# amplifier.net
KiCad netlist of a schematic drawn in EAGLE
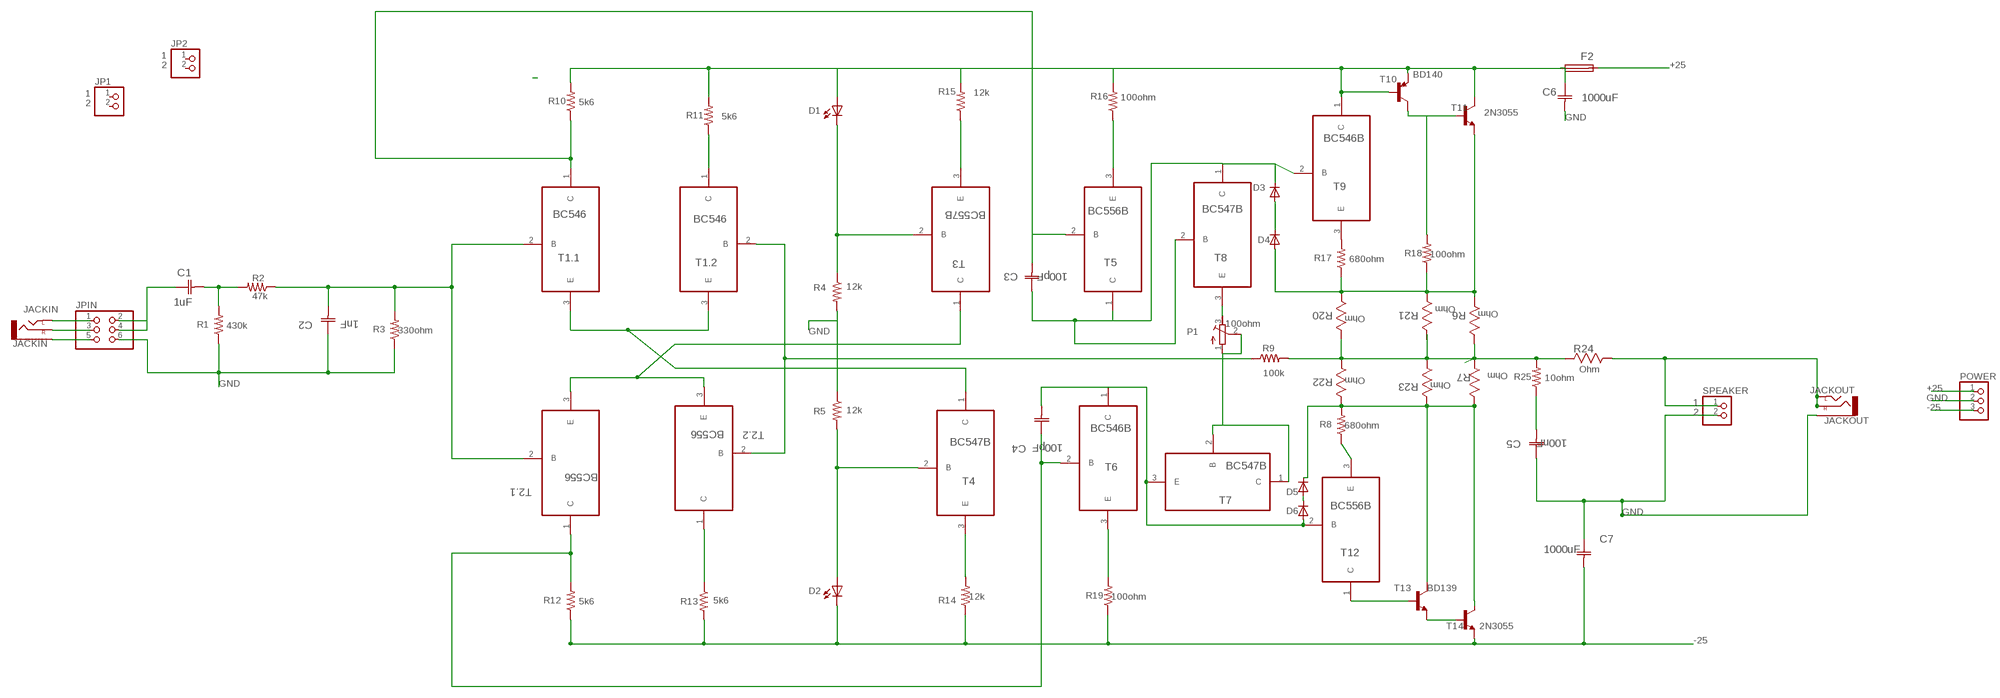
[diagram p0: schematic, sheet 1]

(export (version "E")
  (design (tool "Eeschema 10.0.6"))
  (components
    (comp (ref "C1")
      (value "1uF")
      (footprint "eagle-import:CAPCP3216X180N")
      (fields
        (field (name "MPN") "TPSA226K006R0500")
        (field (name "MPN_1") "TPSA226K006R0500")
        (field (name "OC_FARNELL") "-")
        (field (name "OC_NEWARK") "75M9217")
        (field (name "VOLTAGERATING") "6.3V")
      )
      (libsource (lib "eagle-import") (part "TPSA226K006R0500"))
    )
    (comp (ref "C2")
      (value "1nF")
      (footprint "eagle-import:CAPC2012X130N")
      (fields (field (name "MPN") "0805AC102KAT1A") (field (name "TOLERANCE") "±10%"))
      (libsource (lib "eagle-import") (part "0805AC102KAT1A"))
    )
    (comp (ref "C3")
      (value "100pF")
      (footprint "eagle-import:CAPC2012X130N")
      (fields (field (name "MPN") "0805AC102KAT1A") (field (name "TOLERANCE") "±10%"))
      (libsource (lib "eagle-import") (part "0805AC102KAT1A"))
    )
    (comp (ref "C4")
      (value "100pF")
      (footprint "eagle-import:CAPC2012X130N")
      (fields (field (name "MPN") "0805AC102KAT1A") (field (name "TOLERANCE") "±10%"))
      (libsource (lib "eagle-import") (part "0805AC102KAT1A"))
    )
    (comp (ref "C5")
      (value "100nF")
      (footprint "eagle-import:CAPC2012X130N")
      (fields (field (name "MPN") "0805AC102KAT1A") (field (name "TOLERANCE") "±10%"))
      (libsource (lib "eagle-import") (part "0805AC102KAT1A"))
    )
    (comp (ref "C6")
      (value "1000uF")
      (footprint "eagle-import:CAPC2012X130N")
      (fields (field (name "MPN") "0805AC102KAT1A") (field (name "TOLERANCE") "±10%"))
      (libsource (lib "eagle-import") (part "0805AC102KAT1A"))
    )
    (comp (ref "C7")
      (value "1000uF")
      (footprint "eagle-import:CAPC2012X130N")
      (fields (field (name "MPN") "0805AC102KAT1A") (field (name "TOLERANCE") "±10%"))
      (libsource (lib "eagle-import") (part "0805AC102KAT1A"))
    )
    (comp (ref "D1")
      (value "LED5MM")
      (footprint "eagle-import:LED5MM")
      (libsource (lib "eagle-import") (part "LED5MM"))
    )
    (comp (ref "D2")
      (value "LED5MM")
      (footprint "eagle-import:LED5MM")
      (libsource (lib "eagle-import") (part "LED5MM"))
    )
    (comp (ref "D3")
      (value "1N4148DO35-10")
      (footprint "eagle-import:DO35-10")
      (libsource (lib "eagle-import") (part "1N4148DO35-10"))
    )
    (comp (ref "D4")
      (value "1N4148DO35-10")
      (footprint "eagle-import:DO35-10")
      (libsource (lib "eagle-import") (part "1N4148DO35-10"))
    )
    (comp (ref "D5")
      (value "1N4148DO35-10")
      (footprint "eagle-import:DO35-10")
      (libsource (lib "eagle-import") (part "1N4148DO35-10"))
    )
    (comp (ref "D6")
      (value "1N4148DO35-10")
      (footprint "eagle-import:DO35-10")
      (libsource (lib "eagle-import") (part "1N4148DO35-10"))
    )
    (comp (ref "F2")
      (value "FUSEBLANK_5X20MM")
      (footprint "eagle-import:FUSE_HOLDER_5X20MM")
      (fields (field (name "OC_FARNELL") "unknown") (field (name "OC_NEWARK") "unknown"))
      (libsource (lib "eagle-import") (part "FUSEBLANK_5X20MM"))
    )
    (comp (ref "JACKIN")
      (value "JACKIN")
      (footprint "eagle-import:STEREOJACK2.5MM_STEREOJACK2.5MM")
      (libsource (lib "eagle-import") (part "AUDIO-JACK2.5MM"))
    )
    (comp (ref "JACKOUT")
      (value "JACKOUT")
      (footprint "eagle-import:STEREOJACK2.5MM_STEREOJACK2.5MM")
      (libsource (lib "eagle-import") (part "AUDIO-JACK2.5MM"))
    )
    (comp (ref "JP1")
      (value "PINHD-1X2")
      (footprint "eagle-import:1X02")
      (libsource (lib "eagle-import") (part "PINHD-1X2"))
    )
    (comp (ref "JP2")
      (value "PINHD-1X2")
      (footprint "eagle-import:1X02")
      (libsource (lib "eagle-import") (part "PINHD-1X2"))
    )
    (comp (ref "JPIN")
      (value "PINHD-2X3/90")
      (footprint "eagle-import:2X03_90")
      (libsource (lib "eagle-import") (part "PINHD-2X3/90"))
    )
    (comp (ref "P1")
      (value "100ohm")
      (footprint "eagle-import:RTRIM74X")
      (libsource (lib "eagle-import") (part "R-TRIMM74X"))
    )
    (comp (ref "POWER")
      (value "PINHD-1X3/90")
      (footprint "eagle-import:1X03_90")
      (libsource (lib "eagle-import") (part "PINHD-1X3/90"))
    )
    (comp (ref "R1")
      (value "430k")
      (footprint "eagle-import:AXIAL-0.8")
      (libsource (lib "eagle-import") (part "RESISTORPTH-2W"))
    )
    (comp (ref "R2")
      (value "47k")
      (footprint "eagle-import:AXIAL-0.8")
      (libsource (lib "eagle-import") (part "RESISTORPTH-2W"))
    )
    (comp (ref "R3")
      (value "330ohm")
      (footprint "eagle-import:AXIAL-0.8")
      (libsource (lib "eagle-import") (part "RESISTORPTH-2W"))
    )
    (comp (ref "R4")
      (value "12k")
      (footprint "eagle-import:AXIAL-0.8")
      (libsource (lib "eagle-import") (part "RESISTORPTH-2W"))
    )
    (comp (ref "R5")
      (value "12k")
      (footprint "eagle-import:AXIAL-0.8")
      (libsource (lib "eagle-import") (part "RESISTORPTH-2W"))
    )
    (comp (ref "R6")
      (value "Ohm")
      (footprint "eagle-import:RESC2013X65N")
      (fields (field (name "MPN") "CRM0805-FW-R050ELF") (field (name "TOLERANCE") "±1 %"))
      (libsource (lib "eagle-import") (part "CRM0805-FW-R050ELF"))
    )
    (comp (ref "R7")
      (value "Ohm")
      (footprint "eagle-import:RESC2013X65N")
      (fields (field (name "MPN") "CRM0805-FW-R050ELF") (field (name "TOLERANCE") "±1 %"))
      (libsource (lib "eagle-import") (part "CRM0805-FW-R050ELF"))
    )
    (comp (ref "R8")
      (value "680ohm")
      (footprint "eagle-import:AXIAL-0.8")
      (libsource (lib "eagle-import") (part "RESISTORPTH-2W"))
    )
    (comp (ref "R9")
      (value "100k")
      (footprint "eagle-import:AXIAL-0.8")
      (libsource (lib "eagle-import") (part "RESISTORPTH-2W"))
    )
    (comp (ref "R10")
      (value "5k6")
      (footprint "eagle-import:AXIAL-0.8")
      (libsource (lib "eagle-import") (part "RESISTORPTH-2W"))
    )
    (comp (ref "R11")
      (value "5k6")
      (footprint "eagle-import:AXIAL-0.8")
      (libsource (lib "eagle-import") (part "RESISTORPTH-2W"))
    )
    (comp (ref "R12")
      (value "5k6")
      (footprint "eagle-import:AXIAL-0.8")
      (libsource (lib "eagle-import") (part "RESISTORPTH-2W"))
    )
    (comp (ref "R13")
      (value "5k6")
      (footprint "eagle-import:AXIAL-0.8")
      (libsource (lib "eagle-import") (part "RESISTORPTH-2W"))
    )
    (comp (ref "R14")
      (value "12k")
      (footprint "eagle-import:AXIAL-0.8")
      (libsource (lib "eagle-import") (part "RESISTORPTH-2W"))
    )
    (comp (ref "R15")
      (value "12k")
      (footprint "eagle-import:AXIAL-0.8")
      (libsource (lib "eagle-import") (part "RESISTORPTH-2W"))
    )
    (comp (ref "R16")
      (value "100ohm")
      (footprint "eagle-import:AXIAL-0.8")
      (libsource (lib "eagle-import") (part "RESISTORPTH-2W"))
    )
    (comp (ref "R17")
      (value "680ohm")
      (footprint "eagle-import:AXIAL-0.8")
      (libsource (lib "eagle-import") (part "RESISTORPTH-2W"))
    )
    (comp (ref "R18")
      (value "100ohm")
      (footprint "eagle-import:AXIAL-0.8")
      (libsource (lib "eagle-import") (part "RESISTORPTH-2W"))
    )
    (comp (ref "R19")
      (value "100ohm")
      (footprint "eagle-import:AXIAL-0.8")
      (libsource (lib "eagle-import") (part "RESISTORPTH-2W"))
    )
    (comp (ref "R20")
      (value "Ohm")
      (footprint "eagle-import:RESC2013X65N")
      (fields (field (name "MPN") "CRM0805-FW-R050ELF") (field (name "TOLERANCE") "±1 %"))
      (libsource (lib "eagle-import") (part "CRM0805-FW-R050ELF"))
    )
    (comp (ref "R21")
      (value "Ohm")
      (footprint "eagle-import:RESC2013X65N")
      (fields (field (name "MPN") "CRM0805-FW-R050ELF") (field (name "TOLERANCE") "±1 %"))
      (libsource (lib "eagle-import") (part "CRM0805-FW-R050ELF"))
    )
    (comp (ref "R22")
      (value "Ohm")
      (footprint "eagle-import:RESC2013X65N")
      (fields (field (name "MPN") "CRM0805-FW-R050ELF") (field (name "TOLERANCE") "±1 %"))
      (libsource (lib "eagle-import") (part "CRM0805-FW-R050ELF"))
    )
    (comp (ref "R23")
      (value "Ohm")
      (footprint "eagle-import:RESC2013X65N")
      (fields (field (name "MPN") "CRM0805-FW-R050ELF") (field (name "TOLERANCE") "±1 %"))
      (libsource (lib "eagle-import") (part "CRM0805-FW-R050ELF"))
    )
    (comp (ref "R24")
      (value "Ohm")
      (footprint "eagle-import:RESC2013X65N")
      (fields (field (name "MPN") "CRM0805-FW-R050ELF") (field (name "TOLERANCE") "±1 %"))
      (libsource (lib "eagle-import") (part "CRM0805-FW-R050ELF"))
    )
    (comp (ref "R25")
      (value "10ohm")
      (footprint "eagle-import:AXIAL-0.8")
      (libsource (lib "eagle-import") (part "RESISTORPTH-2W"))
    )
    (comp (ref "SPEAKER")
      (value "PINHD-1X2/90")
      (footprint "eagle-import:1X02_90")
      (libsource (lib "eagle-import") (part "PINHD-1X2/90"))
    )
    (comp (ref "T1.1")
      (value "BC546")
      (footprint "eagle-import:TO127P254X732-3")
      (fields (field (name "MPN") "BC546B"))
      (libsource (lib "eagle-import") (part "BC546B"))
    )
    (comp (ref "T1.2")
      (value "BC546")
      (footprint "eagle-import:TO127P254X732-3")
      (fields (field (name "MPN") "BC546B"))
      (libsource (lib "eagle-import") (part "BC546B"))
    )
    (comp (ref "T2.1")
      (value "BC556")
      (footprint "eagle-import:TO127P254X732-3")
      (fields (field (name "MPN") "BC556B"))
      (libsource (lib "eagle-import") (part "BC556B"))
    )
    (comp (ref "T2.2")
      (value "BC556")
      (footprint "eagle-import:TO127P254X732-3")
      (fields (field (name "MPN") "BC556B"))
      (libsource (lib "eagle-import") (part "BC556B"))
    )
    (comp (ref "T3")
      (value "BC557B")
      (footprint "eagle-import:TO127P254X732-3")
      (libsource (lib "eagle-import") (part "BC557B"))
    )
    (comp (ref "T4")
      (value "BC547B")
      (footprint "eagle-import:TO127P254X732-3")
      (libsource (lib "eagle-import") (part "BC547B"))
    )
    (comp (ref "T5")
      (value "BC556B")
      (footprint "eagle-import:TO127P254X732-3")
      (libsource (lib "eagle-import") (part "BC556B"))
    )
    (comp (ref "T6")
      (value "BC546B")
      (footprint "eagle-import:TO127P254X732-3")
      (libsource (lib "eagle-import") (part "BC546B"))
    )
    (comp (ref "T7")
      (value "BC547B")
      (footprint "eagle-import:TO127P254X732-3")
      (libsource (lib "eagle-import") (part "BC547B"))
    )
    (comp (ref "T8")
      (value "BC547B")
      (footprint "eagle-import:TO127P254X732-3")
      (libsource (lib "eagle-import") (part "BC547B"))
    )
    (comp (ref "T9")
      (value "BC546B")
      (footprint "eagle-import:TO127P254X732-3")
      (libsource (lib "eagle-import") (part "BC546B"))
    )
    (comp (ref "T10")
      (value "BD140")
      (footprint "eagle-import:TO126")
      (libsource (lib "eagle-import") (part "BD140"))
    )
    (comp (ref "T11")
      (value "2N3055")
      (footprint "eagle-import:TO3")
      (libsource (lib "eagle-import") (part "2N3055"))
    )
    (comp (ref "T12")
      (value "BC556B")
      (footprint "eagle-import:TO127P254X732-3")
      (libsource (lib "eagle-import") (part "BC556B"))
    )
    (comp (ref "T13")
      (value "BD139")
      (footprint "eagle-import:TO126")
      (libsource (lib "eagle-import") (part "BD139"))
    )
    (comp (ref "T14")
      (value "2N3055")
      (footprint "eagle-import:TO3")
      (libsource (lib "eagle-import") (part "2N3055"))
    )
  )
  (nets
    (net (code "1") (name "/+25") (class "Default")
      (node (ref "F2") (pin "2") (pinfunction "2_2") (pintype "passive"))
      (node (ref "POWER") (pin "1") (pinfunction "1_1") (pintype "passive"))
    )
    (net (code "2") (name "/-25") (class "Default")
      (node (ref "C7") (pin "2") (pinfunction "C2_2") (pintype "passive"))
      (node (ref "D2") (pin "K") (pinfunction "C_K") (pintype "passive"))
      (node (ref "POWER") (pin "3") (pinfunction "3_3") (pintype "passive"))
      (node (ref "R12") (pin "P$1") (pinfunction "1_P$1") (pintype "passive"))
      (node (ref "R13") (pin "P$2") (pinfunction "2_P$2") (pintype "passive"))
      (node (ref "R14") (pin "P$1") (pinfunction "1_P$1") (pintype "passive"))
      (node (ref "R19") (pin "P$1") (pinfunction "1_P$1") (pintype "passive"))
      (node (ref "T14") (pin "E") (pinfunction "E_E") (pintype "passive"))
    )
    (net (code "3") (name "/GND") (class "Default")
      (node (ref "C2") (pin "1") (pinfunction "C1_1") (pintype "passive"))
      (node (ref "C5") (pin "1") (pinfunction "C1_1") (pintype "passive"))
      (node (ref "C6") (pin "2") (pinfunction "C2_2") (pintype "passive"))
      (node (ref "C7") (pin "1") (pinfunction "C1_1") (pintype "passive"))
      (node (ref "JACKOUT") (pin "RING1") (pinfunction "SLEEVE_RING1") (pintype "bidirectional"))
      (node (ref "JPIN") (pin "6") (pinfunction "6_6") (pintype "passive"))
      (node (ref "POWER") (pin "2") (pinfunction "2_2") (pintype "passive"))
      (node (ref "R1") (pin "P$1") (pinfunction "1_P$1") (pintype "passive"))
      (node (ref "R3") (pin "P$1") (pinfunction "1_P$1") (pintype "passive"))
      (node (ref "R4") (pin "P$2") (pinfunction "2_P$2") (pintype "passive"))
      (node (ref "R5") (pin "P$1") (pinfunction "1_P$1") (pintype "passive"))
      (node (ref "SPEAKER") (pin "2") (pinfunction "2_2") (pintype "passive"))
    )
    (net (code "4") (name "Net-(C1-C1)") (class "Default")
      (node (ref "C1") (pin "1") (pinfunction "C1_1") (pintype "passive"))
      (node (ref "JPIN") (pin "2") (pinfunction "2_2") (pintype "passive"))
      (node (ref "JPIN") (pin "4") (pinfunction "4_4") (pintype "passive"))
    )
    (net (code "5") (name "Net-(C1-C2)") (class "Default")
      (node (ref "C1") (pin "2") (pinfunction "C2_2") (pintype "passive"))
      (node (ref "R1") (pin "P$2") (pinfunction "2_P$2") (pintype "passive"))
      (node (ref "R2") (pin "P$2") (pinfunction "2_P$2") (pintype "passive"))
    )
    (net (code "6") (name "Net-(C2-C2)") (class "Default")
      (node (ref "C2") (pin "2") (pinfunction "C2_2") (pintype "passive"))
      (node (ref "R2") (pin "P$1") (pinfunction "1_P$1") (pintype "passive"))
      (node (ref "R3") (pin "P$2") (pinfunction "2_P$2") (pintype "passive"))
      (node (ref "T1.1") (pin "2") (pinfunction "B_2") (pintype "passive"))
      (node (ref "T2.1") (pin "2") (pinfunction "B_2") (pintype "passive"))
    )
    (net (code "7") (name "Net-(C3-C1)") (class "Default")
      (node (ref "C3") (pin "1") (pinfunction "C1_1") (pintype "passive"))
      (node (ref "D3") (pin "C") (pinfunction "C_C") (pintype "passive"))
      (node (ref "T5") (pin "1") (pinfunction "C_1") (pintype "passive"))
      (node (ref "T8") (pin "1") (pinfunction "C_1") (pintype "passive"))
      (node (ref "T8") (pin "2") (pinfunction "B_2") (pintype "passive"))
      (node (ref "T9") (pin "2") (pinfunction "B_2") (pintype "passive"))
    )
    (net (code "8") (name "Net-(C3-C2)") (class "Default")
      (node (ref "C3") (pin "2") (pinfunction "C2_2") (pintype "passive"))
      (node (ref "R10") (pin "P$1") (pinfunction "1_P$1") (pintype "passive"))
      (node (ref "T1.1") (pin "1") (pinfunction "C_1") (pintype "passive"))
      (node (ref "T5") (pin "2") (pinfunction "B_2") (pintype "passive"))
    )
    (net (code "9") (name "Net-(C4-C1)") (class "Default")
      (node (ref "C4") (pin "1") (pinfunction "C1_1") (pintype "passive"))
      (node (ref "R12") (pin "P$2") (pinfunction "2_P$2") (pintype "passive"))
      (node (ref "T2.1") (pin "1") (pinfunction "C_1") (pintype "passive"))
      (node (ref "T6") (pin "2") (pinfunction "B_2") (pintype "passive"))
    )
    (net (code "10") (name "Net-(C4-C2)") (class "Default")
      (node (ref "C4") (pin "2") (pinfunction "C2_2") (pintype "passive"))
      (node (ref "D6") (pin "A") (pinfunction "A_A") (pintype "passive"))
      (node (ref "T12") (pin "2") (pinfunction "B_2") (pintype "passive"))
      (node (ref "T6") (pin "1") (pinfunction "C_1") (pintype "passive"))
      (node (ref "T7") (pin "3") (pinfunction "E_3") (pintype "passive"))
    )
    (net (code "11") (name "Net-(C5-C2)") (class "Default")
      (node (ref "C5") (pin "2") (pinfunction "C2_2") (pintype "passive"))
      (node (ref "R25") (pin "P$1") (pinfunction "1_P$1") (pintype "passive"))
    )
    (net (code "12") (name "Net-(C6-C1)") (class "Default")
      (node (ref "C6") (pin "1") (pinfunction "C1_1") (pintype "passive"))
      (node (ref "D1") (pin "A") (pinfunction "A_A") (pintype "passive"))
      (node (ref "F2") (pin "1") (pinfunction "1_1") (pintype "passive"))
      (node (ref "R10") (pin "P$2") (pinfunction "2_P$2") (pintype "passive"))
      (node (ref "R11") (pin "P$2") (pinfunction "2_P$2") (pintype "passive"))
      (node (ref "R15") (pin "P$2") (pinfunction "2_P$2") (pintype "passive"))
      (node (ref "R16") (pin "P$2") (pinfunction "2_P$2") (pintype "passive"))
      (node (ref "T10") (pin "1") (pinfunction "E_1") (pintype "passive"))
      (node (ref "T10") (pin "3") (pinfunction "B_3") (pintype "passive"))
      (node (ref "T11") (pin "C") (pinfunction "C_C") (pintype "passive"))
      (node (ref "T11") (pin "C/") (pinfunction "C_C/") (pintype "passive"))
      (node (ref "T9") (pin "1") (pinfunction "C_1") (pintype "passive"))
    )
    (net (code "13") (name "Net-(D1-C)") (class "Default")
      (node (ref "D1") (pin "K") (pinfunction "C_K") (pintype "passive"))
      (node (ref "R4") (pin "P$1") (pinfunction "1_P$1") (pintype "passive"))
      (node (ref "T3") (pin "2") (pinfunction "B_2") (pintype "passive"))
    )
    (net (code "14") (name "Net-(D3-PadA)") (class "Default")
      (node (ref "D3") (pin "A") (pinfunction "A_A") (pintype "passive"))
      (node (ref "D4") (pin "C") (pinfunction "C_C") (pintype "passive"))
    )
    (net (code "15") (name "Net-(D5-PadA)") (class "Default")
      (node (ref "D5") (pin "A") (pinfunction "A_A") (pintype "passive"))
      (node (ref "D6") (pin "C") (pinfunction "C_C") (pintype "passive"))
    )
    (net (code "16") (name "Net-(JACKIN-LEFT)") (class "Default")
      (node (ref "JACKIN") (pin "SHIELD") (pinfunction "LEFT_SHIELD") (pintype "bidirectional"))
      (node (ref "JPIN") (pin "1") (pinfunction "1_1") (pintype "passive"))
    )
    (net (code "17") (name "Net-(JACKIN-RIGHT)") (class "Default")
      (node (ref "JACKIN") (pin "TIP") (pinfunction "RIGHT_TIP") (pintype "bidirectional"))
      (node (ref "JPIN") (pin "3") (pinfunction "3_3") (pintype "passive"))
    )
    (net (code "18") (name "Net-(JACKIN-SLEEVE)") (class "Default")
      (node (ref "JACKIN") (pin "RING1") (pinfunction "SLEEVE_RING1") (pintype "bidirectional"))
      (node (ref "JPIN") (pin "5") (pinfunction "5_5") (pintype "passive"))
    )
    (net (code "19") (name "Net-(JACKOUT-LEFT)") (class "Default")
      (node (ref "JACKOUT") (pin "SHIELD") (pinfunction "LEFT_SHIELD") (pintype "bidirectional"))
      (node (ref "JACKOUT") (pin "TIP") (pinfunction "RIGHT_TIP") (pintype "bidirectional"))
      (node (ref "R24") (pin "1") (pinfunction "R1_1") (pintype "passive"))
      (node (ref "SPEAKER") (pin "1") (pinfunction "1_1") (pintype "passive"))
    )
    (net (code "20") (name "Net-(P1-A)") (class "Default")
      (node (ref "P1") (pin "1") (pinfunction "A_1") (pintype "passive"))
      (node (ref "P1") (pin "2") (pinfunction "S_2") (pintype "passive"))
      (node (ref "R9") (pin "P$1") (pinfunction "1_P$1") (pintype "passive"))
      (node (ref "T1.2") (pin "2") (pinfunction "B_2") (pintype "passive"))
      (node (ref "T2.2") (pin "2") (pinfunction "B_2") (pintype "passive"))
      (node (ref "T7") (pin "1") (pinfunction "C_1") (pintype "passive"))
      (node (ref "T7") (pin "2") (pinfunction "B_2") (pintype "passive"))
    )
    (net (code "21") (name "Net-(P1-E)") (class "Default")
      (node (ref "P1") (pin "3") (pinfunction "E_3") (pintype "passive"))
      (node (ref "T8") (pin "3") (pinfunction "E_3") (pintype "passive"))
    )
    (net (code "22") (name "Net-(R5-2)") (class "Default")
      (node (ref "D2") (pin "A") (pinfunction "A_A") (pintype "passive"))
      (node (ref "R5") (pin "P$2") (pinfunction "2_P$2") (pintype "passive"))
      (node (ref "T4") (pin "2") (pinfunction "B_2") (pintype "passive"))
    )
    (net (code "23") (name "Net-(R8-1)") (class "Default")
      (node (ref "R8") (pin "P$1") (pinfunction "1_P$1") (pintype "passive"))
      (node (ref "T12") (pin "3") (pinfunction "E_3") (pintype "passive"))
    )
    (net (code "24") (name "Net-(R11-1)") (class "Default")
      (node (ref "R11") (pin "P$1") (pinfunction "1_P$1") (pintype "passive"))
      (node (ref "T1.2") (pin "1") (pinfunction "C_1") (pintype "passive"))
    )
    (net (code "25") (name "Net-(R13-1)") (class "Default")
      (node (ref "R13") (pin "P$1") (pinfunction "1_P$1") (pintype "passive"))
      (node (ref "T2.2") (pin "1") (pinfunction "C_1") (pintype "passive"))
    )
    (net (code "26") (name "Net-(R14-2)") (class "Default")
      (node (ref "R14") (pin "P$2") (pinfunction "2_P$2") (pintype "passive"))
      (node (ref "T4") (pin "3") (pinfunction "E_3") (pintype "passive"))
    )
    (net (code "27") (name "Net-(R15-1)") (class "Default")
      (node (ref "R15") (pin "P$1") (pinfunction "1_P$1") (pintype "passive"))
      (node (ref "T3") (pin "3") (pinfunction "E_3") (pintype "passive"))
    )
    (net (code "28") (name "Net-(R16-1)") (class "Default")
      (node (ref "R16") (pin "P$1") (pinfunction "1_P$1") (pintype "passive"))
      (node (ref "T5") (pin "3") (pinfunction "E_3") (pintype "passive"))
    )
    (net (code "29") (name "Net-(R17-1)") (class "Default")
      (node (ref "D4") (pin "A") (pinfunction "A_A") (pintype "passive"))
      (node (ref "R17") (pin "P$1") (pinfunction "1_P$1") (pintype "passive"))
      (node (ref "R18") (pin "P$1") (pinfunction "1_P$1") (pintype "passive"))
      (node (ref "R20") (pin "2") (pinfunction "R2_2") (pintype "passive"))
      (node (ref "R21") (pin "2") (pinfunction "R2_2") (pintype "passive"))
      (node (ref "R6") (pin "2") (pinfunction "R2_2") (pintype "passive"))
      (node (ref "T11") (pin "E") (pinfunction "E_E") (pintype "passive"))
    )
    (net (code "30") (name "Net-(R17-2)") (class "Default")
      (node (ref "R17") (pin "P$2") (pinfunction "2_P$2") (pintype "passive"))
      (node (ref "T9") (pin "3") (pinfunction "E_3") (pintype "passive"))
    )
    (net (code "31") (name "Net-(R18-2)") (class "Default")
      (node (ref "R18") (pin "P$2") (pinfunction "2_P$2") (pintype "passive"))
      (node (ref "T10") (pin "2") (pinfunction "C_2") (pintype "passive"))
      (node (ref "T11") (pin "B") (pinfunction "B_B") (pintype "passive"))
    )
    (net (code "32") (name "Net-(R19-2)") (class "Default")
      (node (ref "R19") (pin "P$2") (pinfunction "2_P$2") (pintype "passive"))
      (node (ref "T6") (pin "3") (pinfunction "E_3") (pintype "passive"))
    )
    (net (code "33") (name "Net-(R20-R1)") (class "Default")
      (node (ref "R20") (pin "1") (pinfunction "R1_1") (pintype "passive"))
      (node (ref "R21") (pin "1") (pinfunction "R1_1") (pintype "passive"))
      (node (ref "R22") (pin "2") (pinfunction "R2_2") (pintype "passive"))
      (node (ref "R23") (pin "2") (pinfunction "R2_2") (pintype "passive"))
      (node (ref "R24") (pin "2") (pinfunction "R2_2") (pintype "passive"))
      (node (ref "R25") (pin "P$2") (pinfunction "2_P$2") (pintype "passive"))
      (node (ref "R6") (pin "1") (pinfunction "R1_1") (pintype "passive"))
      (node (ref "R7") (pin "2") (pinfunction "R2_2") (pintype "passive"))
      (node (ref "R9") (pin "P$2") (pinfunction "2_P$2") (pintype "passive"))
    )
    (net (code "34") (name "Net-(R22-R1)") (class "Default")
      (node (ref "D5") (pin "C") (pinfunction "C_C") (pintype "passive"))
      (node (ref "R22") (pin "1") (pinfunction "R1_1") (pintype "passive"))
      (node (ref "R23") (pin "1") (pinfunction "R1_1") (pintype "passive"))
      (node (ref "R7") (pin "1") (pinfunction "R1_1") (pintype "passive"))
      (node (ref "R8") (pin "P$2") (pinfunction "2_P$2") (pintype "passive"))
      (node (ref "T13") (pin "2") (pinfunction "C_2") (pintype "passive"))
      (node (ref "T14") (pin "C") (pinfunction "C_C") (pintype "passive"))
      (node (ref "T14") (pin "C/") (pinfunction "C_C/") (pintype "passive"))
    )
    (net (code "35") (name "Net-(T1.1-E)") (class "Default")
      (node (ref "T1.1") (pin "3") (pinfunction "E_3") (pintype "passive"))
      (node (ref "T1.2") (pin "3") (pinfunction "E_3") (pintype "passive"))
      (node (ref "T4") (pin "1") (pinfunction "C_1") (pintype "passive"))
    )
    (net (code "36") (name "Net-(T2.1-E)") (class "Default")
      (node (ref "T2.1") (pin "3") (pinfunction "E_3") (pintype "passive"))
      (node (ref "T2.2") (pin "3") (pinfunction "E_3") (pintype "passive"))
      (node (ref "T3") (pin "1") (pinfunction "C_1") (pintype "passive"))
    )
    (net (code "37") (name "Net-(T12-C)") (class "Default")
      (node (ref "T12") (pin "1") (pinfunction "C_1") (pintype "passive"))
      (node (ref "T13") (pin "3") (pinfunction "B_3") (pintype "passive"))
    )
    (net (code "38") (name "Net-(T13-E)") (class "Default")
      (node (ref "T13") (pin "1") (pinfunction "E_1") (pintype "passive"))
      (node (ref "T14") (pin "B") (pinfunction "B_B") (pintype "passive"))
    )
    (net (code "39") (name "unconnected-(JP1-Pad1)") (class "Default")
      (node (ref "JP1") (pin "1") (pinfunction "1_1") (pintype "passive"))
    )
    (net (code "40") (name "unconnected-(JP1-Pad2)") (class "Default")
      (node (ref "JP1") (pin "2") (pinfunction "2_2") (pintype "passive"))
    )
    (net (code "41") (name "unconnected-(JP2-Pad1)") (class "Default")
      (node (ref "JP2") (pin "1") (pinfunction "1_1") (pintype "passive"))
    )
    (net (code "42") (name "unconnected-(JP2-Pad2)") (class "Default")
      (node (ref "JP2") (pin "2") (pinfunction "2_2") (pintype "passive"))
    )
  )
)
